# Phase_Voltage_Dividers.net
KiCad netlist of a schematic drawn in Altium Designer
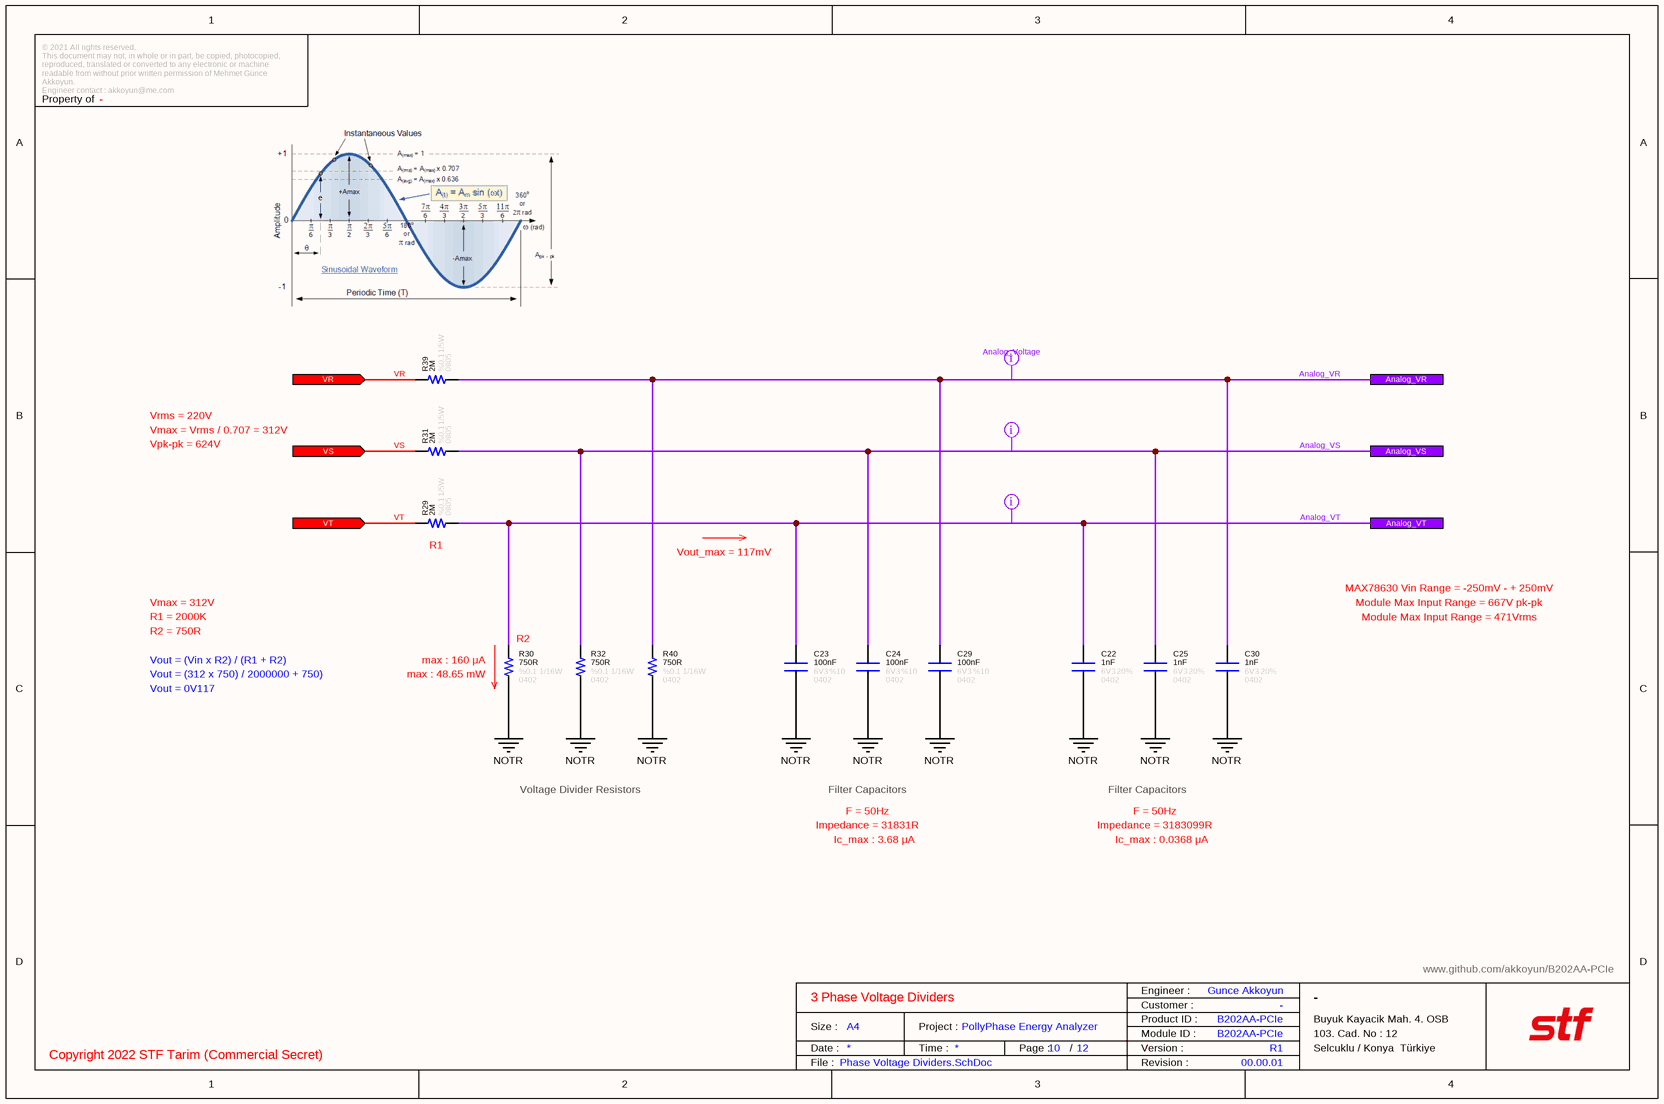
[diagram p0: Phase Voltage Dividers.SchDoc]

(export (version "E")
  (design (tool "Eeschema 10.0.6"))
  (components
    (comp (ref "C22")
      (value "1nF")
      (footprint "CAPACITOR_0402")
      (description "Capacitor - 1nF [0402] (Ceramic)")
      (fields
        (field (name "MANUFACTURER PART NUMBER") "04026C102MAT2A")
        (field (name "TOLERANCE") "20%")
        (field (name "CASE") "0402")
        (field (name "VOLTAGE") "6V3")
      )
      (libsource (lib "Akkoyun") (part "Capacitor - 1nF [0402-6V3]"))
    )
    (comp (ref "C23")
      (value "100nF")
      (footprint "CAPACITOR_0402")
      (description "Capacitor - 100nF [0402-6V3] (Ceramic)")
      (fields
        (field (name "MANUFACTURER PART NUMBER") "04026D104KAT4A")
        (field (name "TOLERANCE") "%10")
        (field (name "VOLTAGE") "6V3")
        (field (name "CASE") "0402")
        (field (name "Comment") "Capacitor - 100nF [0402] (Ceramic)")
      )
      (libsource (lib "Akkoyun") (part "Capacitor - 100nF [0402-6V3]"))
    )
    (comp (ref "C24")
      (value "100nF")
      (footprint "CAPACITOR_0402")
      (description "Capacitor - 100nF [0402-6V3] (Ceramic)")
      (fields
        (field (name "MANUFACTURER PART NUMBER") "04026D104KAT4A")
        (field (name "TOLERANCE") "%10")
        (field (name "VOLTAGE") "6V3")
        (field (name "CASE") "0402")
        (field (name "Comment") "Capacitor - 100nF [0402] (Ceramic)")
      )
      (libsource (lib "Akkoyun") (part "Capacitor - 100nF [0402-6V3]"))
    )
    (comp (ref "C25")
      (value "1nF")
      (footprint "CAPACITOR_0402")
      (description "Capacitor - 1nF [0402] (Ceramic)")
      (fields
        (field (name "MANUFACTURER PART NUMBER") "04026C102MAT2A")
        (field (name "TOLERANCE") "20%")
        (field (name "CASE") "0402")
        (field (name "VOLTAGE") "6V3")
      )
      (libsource (lib "Akkoyun") (part "Capacitor - 1nF [0402-6V3]"))
    )
    (comp (ref "C29")
      (value "100nF")
      (footprint "CAPACITOR_0402")
      (description "Capacitor - 100nF [0402-6V3] (Ceramic)")
      (fields
        (field (name "MANUFACTURER PART NUMBER") "04026D104KAT4A")
        (field (name "TOLERANCE") "%10")
        (field (name "VOLTAGE") "6V3")
        (field (name "CASE") "0402")
        (field (name "Comment") "Capacitor - 100nF [0402] (Ceramic)")
      )
      (libsource (lib "Akkoyun") (part "Capacitor - 100nF [0402-6V3]"))
    )
    (comp (ref "C30")
      (value "1nF")
      (footprint "CAPACITOR_0402")
      (description "Capacitor - 1nF [0402] (Ceramic)")
      (fields
        (field (name "MANUFACTURER PART NUMBER") "04026C102MAT2A")
        (field (name "TOLERANCE") "20%")
        (field (name "CASE") "0402")
        (field (name "VOLTAGE") "6V3")
      )
      (libsource (lib "Akkoyun") (part "Capacitor - 1nF [0402-6V3]"))
    )
    (comp (ref "R29")
      (value "2M")
      (footprint "RESISTOR_0805")
      (description "Thick Film Resistors - SMD 1/5 W 2 MOhm 0.1%")
      (fields
        (field (name "MANUFACTURER PART NUMBER") "MCU0805MD2004BP500")
        (field (name "CASE") "0805")
        (field (name "TOLERANCE") "%0.1")
        (field (name "POWER") "1/5W")
        (field (name "Comment") "2M - 0805 - %0.1 - 1/5W")
      )
      (libsource (lib "Akkoyun") (part "Resistor - 2M [0805] %0.1"))
    )
    (comp (ref "R30")
      (value "750R")
      (footprint "RESISTOR_0402")
      (description "Thick Film Resistors - SMD 1/16 W 750 Ohm 0.1%")
      (fields
        (field (name "MANUFACTURER PART NUMBER") "MCS04020D7500BE000")
        (field (name "CASE") "0402")
        (field (name "TOLERANCE") "%0.1")
        (field (name "POWER") "1/16W")
        (field (name "Comment") "750R - 0402 - %0.1 - 1/16W")
      )
      (libsource (lib "Akkoyun") (part "Resistor - 750R [0402] %0.1"))
    )
    (comp (ref "R31")
      (value "2M")
      (footprint "RESISTOR_0805")
      (description "Thick Film Resistors - SMD 1/5 W 2 MOhm 0.1%")
      (fields
        (field (name "MANUFACTURER PART NUMBER") "MCU0805MD2004BP500")
        (field (name "CASE") "0805")
        (field (name "TOLERANCE") "%0.1")
        (field (name "POWER") "1/5W")
        (field (name "Comment") "2M - 0805 - %0.1 - 1/5W")
      )
      (libsource (lib "Akkoyun") (part "Resistor - 2M [0805] %0.1"))
    )
    (comp (ref "R32")
      (value "750R")
      (footprint "RESISTOR_0402")
      (description "Thick Film Resistors - SMD 1/16 W 750 Ohm 0.1%")
      (fields
        (field (name "MANUFACTURER PART NUMBER") "MCS04020D7500BE000")
        (field (name "CASE") "0402")
        (field (name "TOLERANCE") "%0.1")
        (field (name "POWER") "1/16W")
        (field (name "Comment") "750R - 0402 - %0.1 - 1/16W")
      )
      (libsource (lib "Akkoyun") (part "Resistor - 750R [0402] %0.1"))
    )
    (comp (ref "R39")
      (value "2M")
      (footprint "RESISTOR_0805")
      (description "Thick Film Resistors - SMD 1/5 W 2 MOhm 0.1%")
      (fields
        (field (name "MANUFACTURER PART NUMBER") "MCU0805MD2004BP500")
        (field (name "CASE") "0805")
        (field (name "TOLERANCE") "%0.1")
        (field (name "POWER") "1/5W")
        (field (name "Comment") "2M - 0805 - %0.1 - 1/5W")
      )
      (libsource (lib "Akkoyun") (part "Resistor - 2M [0805] %0.1"))
    )
    (comp (ref "R40")
      (value "750R")
      (footprint "RESISTOR_0402")
      (description "Thick Film Resistors - SMD 1/16 W 750 Ohm 0.1%")
      (fields
        (field (name "MANUFACTURER PART NUMBER") "MCS04020D7500BE000")
        (field (name "CASE") "0402")
        (field (name "TOLERANCE") "%0.1")
        (field (name "POWER") "1/16W")
        (field (name "Comment") "750R - 0402 - %0.1 - 1/16W")
      )
      (libsource (lib "Akkoyun") (part "Resistor - 750R [0402] %0.1"))
    )
  )
  (nets
    (net (code "1") (name "/Analog_VR") (class "Default")
      (node (ref "C29") (pin "2") (pinfunction "2_2") (pintype "passive"))
      (node (ref "C30") (pin "2") (pinfunction "2_2") (pintype "passive"))
      (node (ref "R39") (pin "1") (pinfunction "1_1") (pintype "passive"))
      (node (ref "R40") (pin "2") (pinfunction "2_2") (pintype "passive"))
    )
    (net (code "2") (name "/Analog_VS") (class "Default")
      (node (ref "C24") (pin "2") (pinfunction "2_2") (pintype "passive"))
      (node (ref "C25") (pin "2") (pinfunction "2_2") (pintype "passive"))
      (node (ref "R31") (pin "1") (pinfunction "1_1") (pintype "passive"))
      (node (ref "R32") (pin "2") (pinfunction "2_2") (pintype "passive"))
    )
    (net (code "3") (name "/Analog_VT") (class "Default")
      (node (ref "C22") (pin "2") (pinfunction "2_2") (pintype "passive"))
      (node (ref "C23") (pin "2") (pinfunction "2_2") (pintype "passive"))
      (node (ref "R29") (pin "1") (pinfunction "1_1") (pintype "passive"))
      (node (ref "R30") (pin "2") (pinfunction "2_2") (pintype "passive"))
    )
    (net (code "4") (name "/VR") (class "Default")
      (node (ref "R39") (pin "2") (pinfunction "2_2") (pintype "passive"))
    )
    (net (code "5") (name "/VS") (class "Default")
      (node (ref "R31") (pin "2") (pinfunction "2_2") (pintype "passive"))
    )
    (net (code "6") (name "/VT") (class "Default")
      (node (ref "R29") (pin "2") (pinfunction "2_2") (pintype "passive"))
    )
    (net (code "7") (name "NOTR") (class "Default")
      (node (ref "C22") (pin "1") (pinfunction "1_1") (pintype "passive"))
      (node (ref "C23") (pin "1") (pinfunction "1_1") (pintype "passive"))
      (node (ref "C24") (pin "1") (pinfunction "1_1") (pintype "passive"))
      (node (ref "C25") (pin "1") (pinfunction "1_1") (pintype "passive"))
      (node (ref "C29") (pin "1") (pinfunction "1_1") (pintype "passive"))
      (node (ref "C30") (pin "1") (pinfunction "1_1") (pintype "passive"))
      (node (ref "R30") (pin "1") (pinfunction "1_1") (pintype "passive"))
      (node (ref "R32") (pin "1") (pinfunction "1_1") (pintype "passive"))
      (node (ref "R40") (pin "1") (pinfunction "1_1") (pintype "passive"))
    )
  )
)
